# n-channel-h-bridge-wide.net
KiCad netlist of a schematic drawn in EAGLE
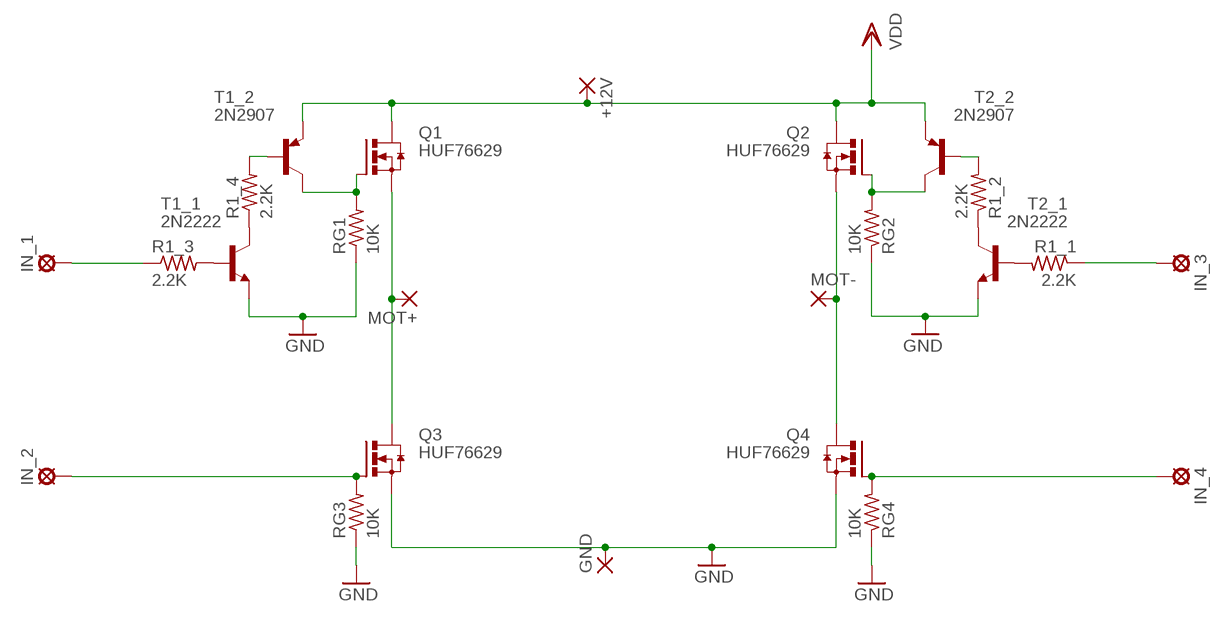
[diagram p0: schematic, sheet 1]

(export (version "E")
  (design (tool "Eeschema 10.0.6"))
  (components
    (comp (ref "+12V")
      (value "WIREPAD4,16O1,6")
      (footprint "eagle-import:4,16O1,6")
      (libsource (lib "eagle-import") (part "WIREPAD4,16O1,6"))
    )
    (comp (ref "GND")
      (value "WIREPAD4,16O1,6")
      (footprint "eagle-import:4,16O1,6")
      (libsource (lib "eagle-import") (part "WIREPAD4,16O1,6"))
    )
    (comp (ref "IN_1")
      (value "LSP11")
      (footprint "eagle-import:LSP11")
      (libsource (lib "eagle-import") (part "LSP11"))
    )
    (comp (ref "IN_2")
      (value "LSP11")
      (footprint "eagle-import:LSP11")
      (libsource (lib "eagle-import") (part "LSP11"))
    )
    (comp (ref "IN_3")
      (value "LSP11")
      (footprint "eagle-import:LSP11")
      (libsource (lib "eagle-import") (part "LSP11"))
    )
    (comp (ref "IN_4")
      (value "LSP11")
      (footprint "eagle-import:LSP11")
      (libsource (lib "eagle-import") (part "LSP11"))
    )
    (comp (ref "MOT+")
      (value "WIREPAD4,16O1,6")
      (footprint "eagle-import:4,16O1,6")
      (libsource (lib "eagle-import") (part "WIREPAD4,16O1,6"))
    )
    (comp (ref "MOT-")
      (value "WIREPAD4,16O1,6")
      (footprint "eagle-import:4,16O1,6")
      (libsource (lib "eagle-import") (part "WIREPAD4,16O1,6"))
    )
    (comp (ref "Q1")
      (value "HUF76629")
      (footprint "eagle-import:D-PAK_TO252")
      (libsource (lib "eagle-import") (part "HUF76629D3ST_F085D-PAK_TO252"))
    )
    (comp (ref "Q2")
      (value "HUF76629")
      (footprint "eagle-import:D-PAK_TO252")
      (libsource (lib "eagle-import") (part "HUF76629D3ST_F085D-PAK_TO252"))
    )
    (comp (ref "Q3")
      (value "HUF76629")
      (footprint "eagle-import:D-PAK_TO252")
      (libsource (lib "eagle-import") (part "HUF76629D3ST_F085D-PAK_TO252"))
    )
    (comp (ref "Q4")
      (value "HUF76629")
      (footprint "eagle-import:D-PAK_TO252")
      (libsource (lib "eagle-import") (part "HUF76629D3ST_F085D-PAK_TO252"))
    )
    (comp (ref "R1_1")
      (value "2.2K")
      (footprint "eagle-import:R0805")
      (libsource (lib "eagle-import") (part "R-US_R0805"))
    )
    (comp (ref "R1_2")
      (value "2.2K")
      (footprint "eagle-import:R0805")
      (libsource (lib "eagle-import") (part "R-US_R0805"))
    )
    (comp (ref "R1_3")
      (value "2.2K")
      (footprint "eagle-import:R0805")
      (libsource (lib "eagle-import") (part "R-US_R0805"))
    )
    (comp (ref "R1_4")
      (value "2.2K")
      (footprint "eagle-import:R0805")
      (libsource (lib "eagle-import") (part "R-US_R0805"))
    )
    (comp (ref "RG1")
      (value "10K")
      (footprint "eagle-import:R0805")
      (libsource (lib "eagle-import") (part "R-US_R0805"))
    )
    (comp (ref "RG2")
      (value "10K")
      (footprint "eagle-import:R0805")
      (libsource (lib "eagle-import") (part "R-US_R0805"))
    )
    (comp (ref "RG3")
      (value "10K")
      (footprint "eagle-import:R0805")
      (libsource (lib "eagle-import") (part "R-US_R0805"))
    )
    (comp (ref "RG4")
      (value "10K")
      (footprint "eagle-import:R0805")
      (libsource (lib "eagle-import") (part "R-US_R0805"))
    )
    (comp (ref "T1_1")
      (value "2N2222")
      (footprint "eagle-import:TO92-EBC-OVAL")
      (libsource (lib "eagle-import") (part "2N2222"))
    )
    (comp (ref "T1_2")
      (value "2N2907")
      (footprint "eagle-import:TO92-EBC-OVAL")
      (libsource (lib "eagle-import") (part "2N2907"))
    )
    (comp (ref "T2_1")
      (value "2N2222")
      (footprint "eagle-import:TO92-EBC-OVAL")
      (libsource (lib "eagle-import") (part "2N2222"))
    )
    (comp (ref "T2_2")
      (value "2N2907")
      (footprint "eagle-import:TO92-EBC-OVAL")
      (libsource (lib "eagle-import") (part "2N2907"))
    )
  )
  (nets
    (net (code "1") (name "GND") (class "Default")
      (node (ref "GND") (pin "1") (pinfunction "P_1") (pintype "passive"))
      (node (ref "Q3") (pin "3") (pinfunction "S_3") (pintype "passive"))
      (node (ref "Q4") (pin "3") (pinfunction "S_3") (pintype "passive"))
      (node (ref "RG1") (pin "1") (pinfunction "1_1") (pintype "passive"))
      (node (ref "RG2") (pin "1") (pinfunction "1_1") (pintype "passive"))
      (node (ref "RG3") (pin "1") (pinfunction "1_1") (pintype "passive"))
      (node (ref "RG4") (pin "1") (pinfunction "1_1") (pintype "passive"))
      (node (ref "T1_1") (pin "E") (pinfunction "E_E") (pintype "passive"))
      (node (ref "T2_1") (pin "E") (pinfunction "E_E") (pintype "passive"))
    )
    (net (code "2") (name "Net-(IN_1-PadMP)") (class "Default")
      (node (ref "IN_1") (pin "MP") (pinfunction "MP_MP") (pintype "passive"))
      (node (ref "R1_3") (pin "1") (pinfunction "1_1") (pintype "passive"))
    )
    (net (code "3") (name "Net-(IN_3-PadMP)") (class "Default")
      (node (ref "IN_3") (pin "MP") (pinfunction "MP_MP") (pintype "passive"))
      (node (ref "R1_1") (pin "1") (pinfunction "1_1") (pintype "passive"))
    )
    (net (code "4") (name "Net-(MOT+-P)") (class "Default")
      (node (ref "MOT+") (pin "1") (pinfunction "P_1") (pintype "passive"))
      (node (ref "Q1") (pin "3") (pinfunction "S_3") (pintype "passive"))
      (node (ref "Q3") (pin "4") (pinfunction "D_4") (pintype "passive"))
    )
    (net (code "5") (name "Net-(MOT--P)") (class "Default")
      (node (ref "MOT-") (pin "1") (pinfunction "P_1") (pintype "passive"))
      (node (ref "Q2") (pin "3") (pinfunction "S_3") (pintype "passive"))
      (node (ref "Q4") (pin "4") (pinfunction "D_4") (pintype "passive"))
    )
    (net (code "6") (name "Net-(Q1-G)") (class "Default")
      (node (ref "Q1") (pin "1") (pinfunction "G_1") (pintype "passive"))
      (node (ref "RG1") (pin "2") (pinfunction "2_2") (pintype "passive"))
      (node (ref "T1_2") (pin "C") (pinfunction "C_C") (pintype "passive"))
    )
    (net (code "7") (name "Net-(Q2-G)") (class "Default")
      (node (ref "Q2") (pin "1") (pinfunction "G_1") (pintype "passive"))
      (node (ref "RG2") (pin "2") (pinfunction "2_2") (pintype "passive"))
      (node (ref "T2_2") (pin "C") (pinfunction "C_C") (pintype "passive"))
    )
    (net (code "8") (name "Net-(Q3-G)") (class "Default")
      (node (ref "IN_2") (pin "MP") (pinfunction "MP_MP") (pintype "passive"))
      (node (ref "Q3") (pin "1") (pinfunction "G_1") (pintype "passive"))
      (node (ref "RG3") (pin "2") (pinfunction "2_2") (pintype "passive"))
    )
    (net (code "9") (name "Net-(Q4-G)") (class "Default")
      (node (ref "IN_4") (pin "MP") (pinfunction "MP_MP") (pintype "passive"))
      (node (ref "Q4") (pin "1") (pinfunction "G_1") (pintype "passive"))
      (node (ref "RG4") (pin "2") (pinfunction "2_2") (pintype "passive"))
    )
    (net (code "10") (name "Net-(R1_1-Pad2)") (class "Default")
      (node (ref "R1_1") (pin "2") (pinfunction "2_2") (pintype "passive"))
      (node (ref "T2_1") (pin "B") (pinfunction "B_B") (pintype "passive"))
    )
    (net (code "11") (name "Net-(R1_2-Pad1)") (class "Default")
      (node (ref "R1_2") (pin "1") (pinfunction "1_1") (pintype "passive"))
      (node (ref "T2_1") (pin "C") (pinfunction "C_C") (pintype "passive"))
    )
    (net (code "12") (name "Net-(R1_2-Pad2)") (class "Default")
      (node (ref "R1_2") (pin "2") (pinfunction "2_2") (pintype "passive"))
      (node (ref "T2_2") (pin "B") (pinfunction "B_B") (pintype "passive"))
    )
    (net (code "13") (name "Net-(R1_3-Pad2)") (class "Default")
      (node (ref "R1_3") (pin "2") (pinfunction "2_2") (pintype "passive"))
      (node (ref "T1_1") (pin "B") (pinfunction "B_B") (pintype "passive"))
    )
    (net (code "14") (name "Net-(R1_4-Pad1)") (class "Default")
      (node (ref "R1_4") (pin "1") (pinfunction "1_1") (pintype "passive"))
      (node (ref "T1_1") (pin "C") (pinfunction "C_C") (pintype "passive"))
    )
    (net (code "15") (name "Net-(R1_4-Pad2)") (class "Default")
      (node (ref "R1_4") (pin "2") (pinfunction "2_2") (pintype "passive"))
      (node (ref "T1_2") (pin "B") (pinfunction "B_B") (pintype "passive"))
    )
    (net (code "16") (name "VDD") (class "Default")
      (node (ref "+12V") (pin "1") (pinfunction "P_1") (pintype "passive"))
      (node (ref "Q1") (pin "4") (pinfunction "D_4") (pintype "passive"))
      (node (ref "Q2") (pin "4") (pinfunction "D_4") (pintype "passive"))
      (node (ref "T1_2") (pin "E") (pinfunction "E_E") (pintype "passive"))
      (node (ref "T2_2") (pin "E") (pinfunction "E_E") (pintype "passive"))
    )
  )
)
